# DSD_SDR_MainBoard_Single.net
KiCad netlist of a schematic drawn in Altium Designer
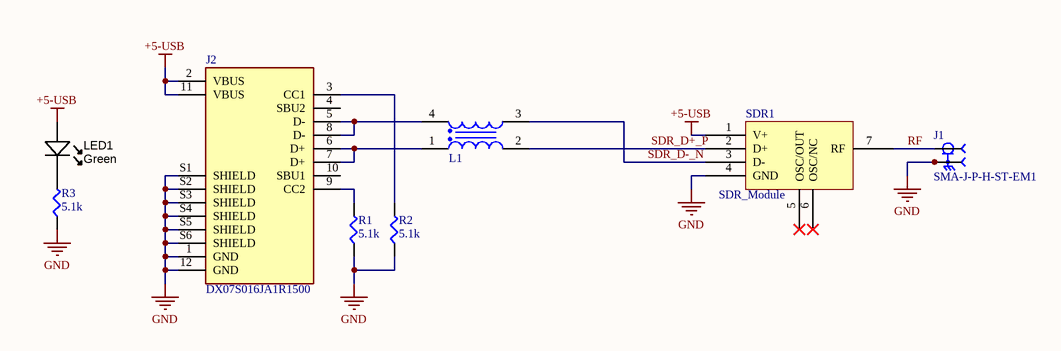
[diagram p0: DSD_SDR_MainBoard_Single.SchDoc]

(export (version "E")
  (design (tool "Eeschema 10.0.6"))
  (components
    (comp (ref "J1")
      (value "SMA-J-P-H-ST-EM1")
      (footprint "SAMTEC_SMA-J-P-H-ST-EM1")
      (description "SMA Connector Jack, Female Socket 50Ohm Board Edge, End Launch Solder")
      (fields (field (name "MF") "Samtec"))
      (libsource (lib "SMA-J-P-H-ST-EM1") (part "SMA-J-P-H-ST-EM1"))
    )
    (comp (ref "J2")
      (value "DX07S016JA1R1500")
      (footprint "JAE_DX07S016JA1R1500")
      (libsource (lib "DX07S016JA1R1500") (part "DX07S016JA1R1500"))
    )
    (comp (ref "L1")
      (value "90Ohm")
      (footprint "WE-CNSW_1206")
      (description "WE-CNSW SMT Common Mode Line Filter, size 1206, 90Ohm, 0.111uH, 50V")
      (fields
        (field (name "MANUFACTURER") "Wurth Elektronik")
        (field (name "MANUFACTURER PART NUMBER") "744232090")
      )
      (libsource (lib "WE-CNSW (rev22a)") (part "744232090"))
    )
    (comp (ref "LED1")
      (value "Green")
      (footprint "LED-0603-GREEN")
      (description "LED 0603 SMD Green 570nm 50mcd 20mA")
      (libsource (lib "PBL - Light Sources") (part "LED_SMD_Green_0603_570nm"))
    )
    (comp (ref "R1")
      (value "5.1k")
      (footprint "SMD-0603-RES")
      (description "RES SMD 5.1K OHM 1% 1/10W 0603")
      (fields
        (field (name "PART NUMBER") "ERJ-3EKF5101V")
        (field (name "DIGI-KEY PART NUMBER") "P5.10KHCT-ND")
      )
      (libsource (lib "res_panasonic_erj_xls") (part "RESISTOR"))
    )
    (comp (ref "R2")
      (value "5.1k")
      (footprint "SMD-0603-RES")
      (description "RES SMD 5.1K OHM 1% 1/10W 0603")
      (fields
        (field (name "PART NUMBER") "ERJ-3EKF5101V")
        (field (name "DIGI-KEY PART NUMBER") "P5.10KHCT-ND")
      )
      (libsource (lib "res_panasonic_erj_xls") (part "RESISTOR"))
    )
    (comp (ref "R3")
      (value "5.1k")
      (footprint "SMD-0603-RES")
      (description "RES SMD 5.1K OHM 1% 1/10W 0603")
      (fields
        (field (name "PART NUMBER") "ERJ-3EKF5101V")
        (field (name "DIGI-KEY PART NUMBER") "P5.10KHCT-ND")
      )
      (libsource (lib "res_panasonic_erj_xls") (part "RESISTOR"))
    )
    (comp (ref "SDR1")
      (value "SDR_Module")
      (footprint "SDR")
      (libsource (lib "SDR_Module") (part "SDR_Module"))
    )
  )
  (nets
    (net (code "1") (name "+5-USB") (class "Default")
      (node (ref "J2") (pin "11") (pinfunction "VBUS_11") (pintype "power_in"))
      (node (ref "J2") (pin "2") (pinfunction "VBUS_2") (pintype "power_in"))
      (node (ref "LED1") (pin "A") (pinfunction "A_A") (pintype "passive"))
      (node (ref "SDR1") (pin "1") (pinfunction "V+_1") (pintype "passive"))
    )
    (net (code "2") (name "/RF") (class "Default")
      (node (ref "J1") (pin "1") (pinfunction "1_1") (pintype "passive"))
      (node (ref "SDR1") (pin "7") (pinfunction "RF_7") (pintype "passive"))
    )
    (net (code "3") (name "/SDR_D+_P") (class "Default")
      (node (ref "L1") (pin "2") (pinfunction "2_2") (pintype "passive"))
      (node (ref "SDR1") (pin "2") (pinfunction "D+_2") (pintype "passive"))
    )
    (net (code "4") (name "/SDR_D-_N") (class "Default")
      (node (ref "L1") (pin "3") (pinfunction "3_3") (pintype "passive"))
      (node (ref "SDR1") (pin "3") (pinfunction "D-_3") (pintype "passive"))
    )
    (net (code "5") (name "GND") (class "Default")
      (node (ref "J1") (pin "2_1") (pinfunction "2_2_1") (pintype "passive"))
      (node (ref "J1") (pin "2_2") (pinfunction "2_2_2") (pintype "passive"))
      (node (ref "J1") (pin "3_1") (pinfunction "2_3_1") (pintype "passive"))
      (node (ref "J1") (pin "3_2") (pinfunction "2_3_2") (pintype "passive"))
      (node (ref "J2") (pin "1") (pinfunction "GND_1") (pintype "power_in"))
      (node (ref "J2") (pin "12") (pinfunction "GND_12") (pintype "power_in"))
      (node (ref "J2") (pin "S1") (pinfunction "SHIELD_S1") (pintype "passive"))
      (node (ref "J2") (pin "S2") (pinfunction "SHIELD_S2") (pintype "passive"))
      (node (ref "J2") (pin "S3") (pinfunction "SHIELD_S3") (pintype "passive"))
      (node (ref "J2") (pin "S4") (pinfunction "SHIELD_S4") (pintype "passive"))
      (node (ref "J2") (pin "S5") (pinfunction "SHIELD_S5") (pintype "passive"))
      (node (ref "J2") (pin "S6") (pinfunction "SHIELD_S6") (pintype "passive"))
      (node (ref "R1") (pin "1") (pinfunction "1_1") (pintype "passive"))
      (node (ref "R2") (pin "1") (pinfunction "1_1") (pintype "passive"))
      (node (ref "R3") (pin "1") (pinfunction "1_1") (pintype "passive"))
      (node (ref "SDR1") (pin "4") (pinfunction "GND_4") (pintype "passive"))
    )
    (net (code "6") (name "Net-(J2-CC1)") (class "Default")
      (node (ref "J2") (pin "3") (pinfunction "CC1_3") (pintype "passive"))
      (node (ref "R2") (pin "2") (pinfunction "2_2") (pintype "passive"))
    )
    (net (code "7") (name "Net-(J2-CC2)") (class "Default")
      (node (ref "J2") (pin "9") (pinfunction "CC2_9") (pintype "passive"))
      (node (ref "R1") (pin "2") (pinfunction "2_2") (pintype "passive"))
    )
    (net (code "8") (name "Net-(J2-D+-Pad6)") (class "Default")
      (node (ref "J2") (pin "6") (pinfunction "D+_6") (pintype "passive"))
      (node (ref "J2") (pin "7") (pinfunction "D+_7") (pintype "passive"))
      (node (ref "L1") (pin "1") (pinfunction "1_1") (pintype "passive"))
    )
    (net (code "9") (name "Net-(J2-D--Pad5)") (class "Default")
      (node (ref "J2") (pin "5") (pinfunction "D-_5") (pintype "passive"))
      (node (ref "J2") (pin "8") (pinfunction "D-_8") (pintype "passive"))
      (node (ref "L1") (pin "4") (pinfunction "4_4") (pintype "passive"))
    )
    (net (code "10") (name "Net-(LED1-PadK)") (class "Default")
      (node (ref "LED1") (pin "K") (pinfunction "K_K") (pintype "passive"))
      (node (ref "R3") (pin "2") (pinfunction "2_2") (pintype "passive"))
    )
    (net (code "11") (name "unconnected-(J2-SBU1-Pad10)") (class "Default")
      (node (ref "J2") (pin "10") (pinfunction "SBU1_10") (pintype "passive"))
    )
    (net (code "12") (name "unconnected-(J2-SBU2-Pad4)") (class "Default")
      (node (ref "J2") (pin "4") (pinfunction "SBU2_4") (pintype "passive"))
    )
    (net (code "13") (name "unconnected-(SDR1-OSC{slash}NC-Pad6)") (class "Default")
      (node (ref "SDR1") (pin "6") (pinfunction "OSC/NC_6") (pintype "passive+no_connect"))
    )
    (net (code "14") (name "unconnected-(SDR1-OSC{slash}OUT-Pad5)") (class "Default")
      (node (ref "SDR1") (pin "5") (pinfunction "OSC/OUT_5") (pintype "passive+no_connect"))
    )
  )
)
